# generator2.net
KiCad netlist of a schematic drawn in EAGLE
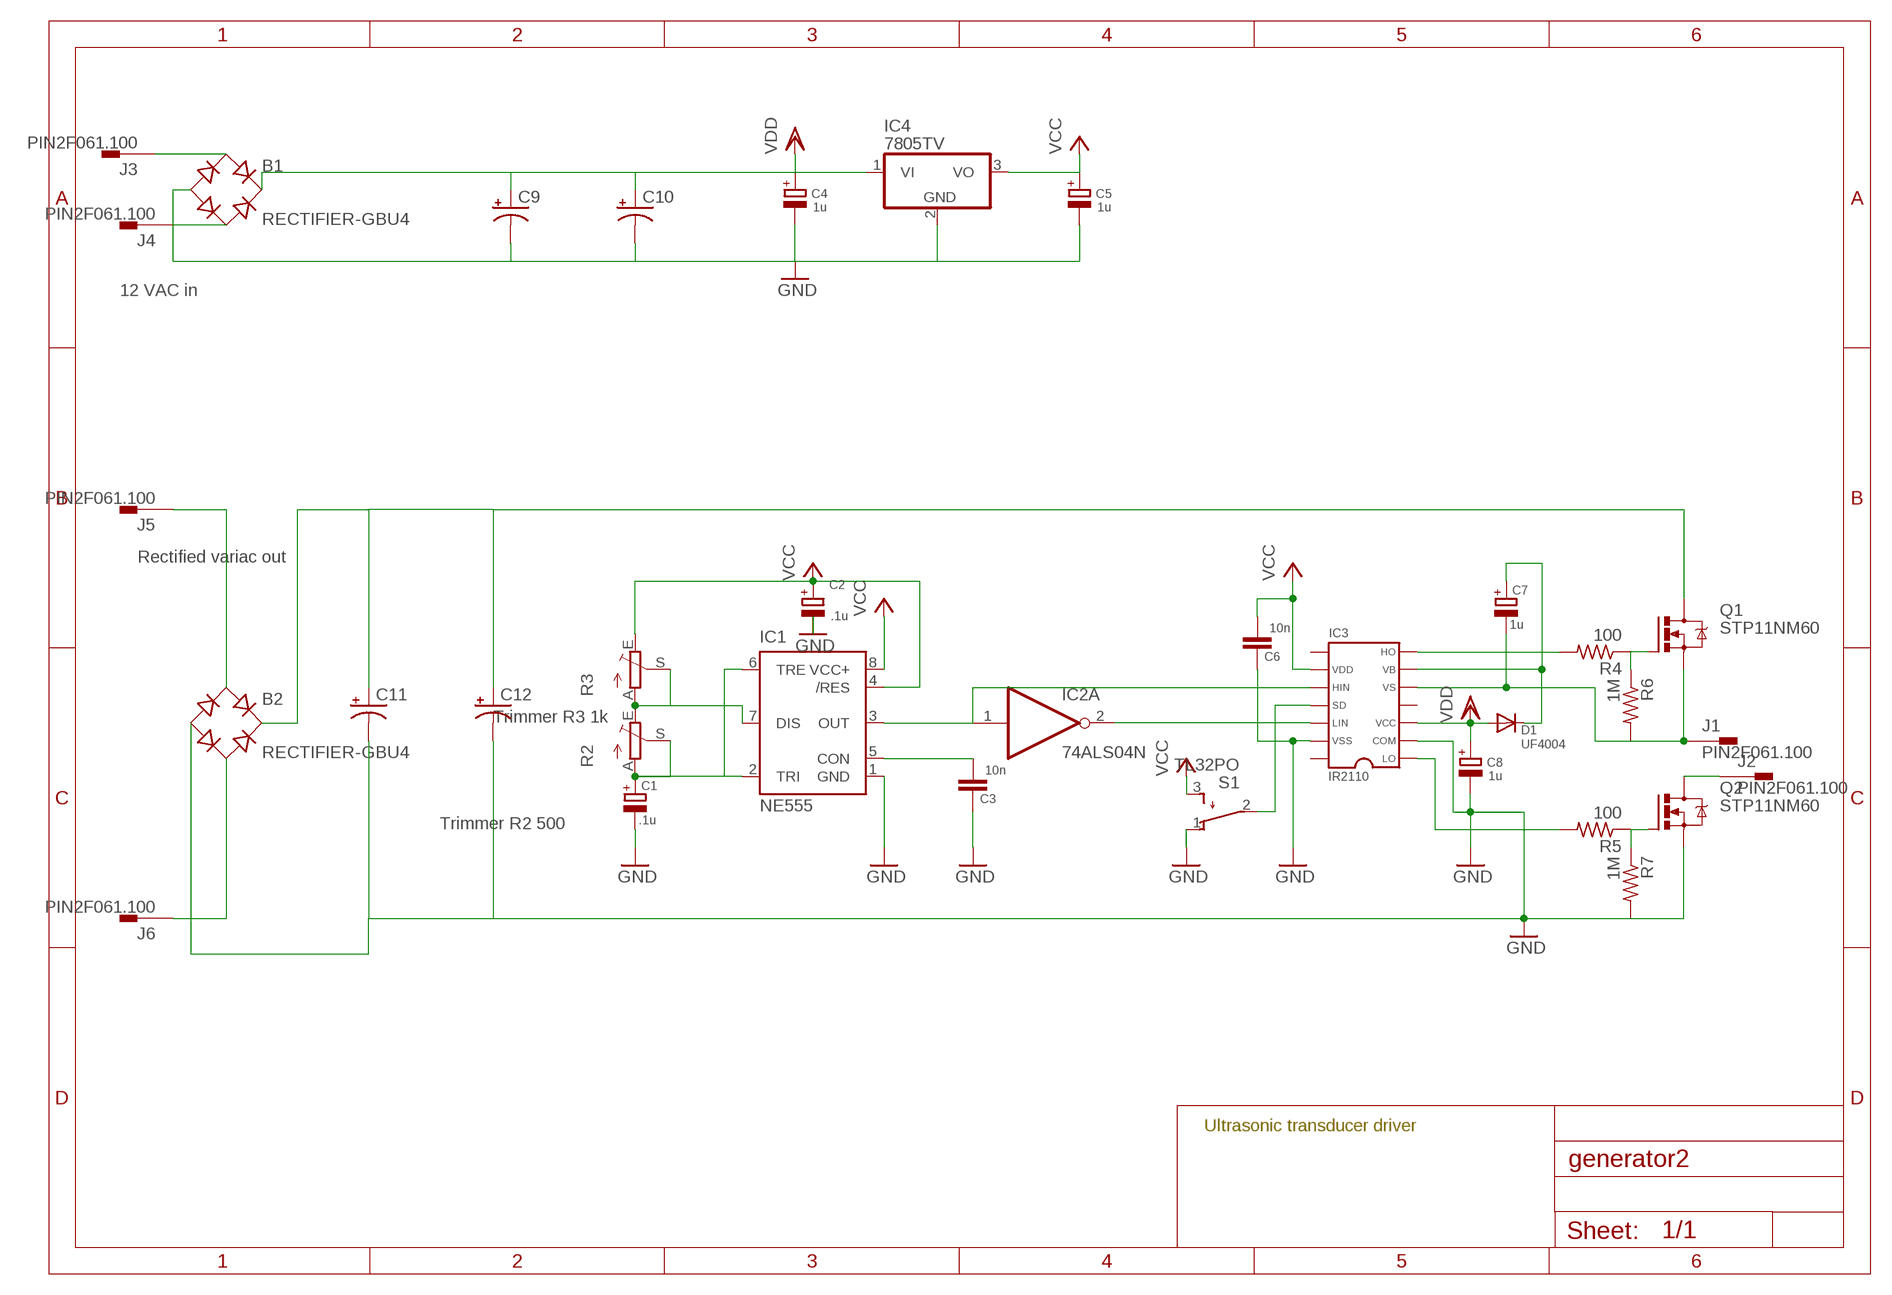
[diagram p0: schematic, sheet 1]

(export (version "E")
  (design (tool "Eeschema 10.0.6"))
  (components
    (comp (ref "B1")
      (value "RECTIFIER-GBU4")
      (footprint "eagle-import:GBU4")
      (libsource (lib "eagle-import") (part "RECTIFIER-GBU4"))
    )
    (comp (ref "B2")
      (value "RECTIFIER-GBU4")
      (footprint "eagle-import:GBU4")
      (libsource (lib "eagle-import") (part "RECTIFIER-GBU4"))
    )
    (comp (ref "C1")
      (value ".1u")
      (footprint "eagle-import:E5-8,5")
      (libsource (lib "eagle-import") (part "CPOL-EUE5-8.5"))
    )
    (comp (ref "C2")
      (value ".1u")
      (footprint "eagle-import:E5-8,5")
      (libsource (lib "eagle-import") (part "CPOL-EUE5-8.5"))
    )
    (comp (ref "C3")
      (value "10n")
      (footprint "eagle-import:C075-052X106")
      (libsource (lib "eagle-import") (part "C-EU075-052X106"))
    )
    (comp (ref "C4")
      (value "1u")
      (footprint "eagle-import:E5-8,5")
      (libsource (lib "eagle-import") (part "CPOL-EUE5-8.5"))
    )
    (comp (ref "C5")
      (value "1u")
      (footprint "eagle-import:E5-8,5")
      (libsource (lib "eagle-import") (part "CPOL-EUE5-8.5"))
    )
    (comp (ref "C6")
      (value "10n")
      (footprint "eagle-import:C075-052X106")
      (libsource (lib "eagle-import") (part "C-EU075-052X106"))
    )
    (comp (ref "C7")
      (value "1u")
      (footprint "eagle-import:E5-8,5")
      (libsource (lib "eagle-import") (part "CPOL-EUE5-8.5"))
    )
    (comp (ref "C8")
      (value "1u")
      (footprint "eagle-import:E5-8,5")
      (libsource (lib "eagle-import") (part "CPOL-EUE5-8.5"))
    )
    (comp (ref "C9")
      (value "CPOL-USE7.5-18")
      (footprint "eagle-import:E7,5-18")
      (libsource (lib "eagle-import") (part "CPOL-USE7.5-18"))
    )
    (comp (ref "C10")
      (value "CPOL-USE7.5-18")
      (footprint "eagle-import:E7,5-18")
      (libsource (lib "eagle-import") (part "CPOL-USE7.5-18"))
    )
    (comp (ref "C11")
      (value "CPOL-USE7.5-18")
      (footprint "eagle-import:E7,5-18")
      (libsource (lib "eagle-import") (part "CPOL-USE7.5-18"))
    )
    (comp (ref "C12")
      (value "CPOL-USE7.5-18")
      (footprint "eagle-import:E7,5-18")
      (libsource (lib "eagle-import") (part "CPOL-USE7.5-18"))
    )
    (comp (ref "D1")
      (value "UF4004")
      (footprint "eagle-import:D-7.5")
      (libsource (lib "eagle-import") (part "DIODE-D-7.5"))
    )
    (comp (ref "IC1")
      (value "NE555")
      (footprint "eagle-import:DIL-08")
      (fields (field (name "MF") "Arrow Electronics") (field (name "MPN") "NE555N"))
      (libsource (lib "eagle-import") (part "NE555"))
    )
    (comp (ref "IC2")
      (value "74ALS04N")
      (footprint "eagle-import:DIL14")
      (libsource (lib "eagle-import") (part "7404NALS"))
    )
    (comp (ref "IC3")
      (value "IR2110")
      (footprint "eagle-import:DIL14")
      (libsource (lib "eagle-import") (part "IR2110"))
    )
    (comp (ref "IC4")
      (value "7805TV")
      (footprint "eagle-import:TO220V")
      (libsource (lib "eagle-import") (part "78TV05"))
    )
    (comp (ref "J1")
      (value "PIN2F061.100")
      (footprint "eagle-import:F061.100")
      (libsource (lib "eagle-import") (part "PIN2F061.100"))
    )
    (comp (ref "J2")
      (value "PIN2F061.100")
      (footprint "eagle-import:F061.100")
      (libsource (lib "eagle-import") (part "PIN2F061.100"))
    )
    (comp (ref "J3")
      (value "PIN2F061.100")
      (footprint "eagle-import:F061.100")
      (libsource (lib "eagle-import") (part "PIN2F061.100"))
    )
    (comp (ref "J4")
      (value "PIN2F061.100")
      (footprint "eagle-import:F061.100")
      (libsource (lib "eagle-import") (part "PIN2F061.100"))
    )
    (comp (ref "J5")
      (value "PIN2F061.100")
      (footprint "eagle-import:F061.100")
      (libsource (lib "eagle-import") (part "PIN2F061.100"))
    )
    (comp (ref "J6")
      (value "PIN2F061.100")
      (footprint "eagle-import:F061.100")
      (libsource (lib "eagle-import") (part "PIN2F061.100"))
    )
    (comp (ref "Q1")
      (value "STP11NM60")
      (footprint "eagle-import:TO220BV")
      (libsource (lib "eagle-import") (part "IRF530"))
    )
    (comp (ref "Q2")
      (value "STP11NM60")
      (footprint "eagle-import:TO220BV")
      (libsource (lib "eagle-import") (part "IRF530"))
    )
    (comp (ref "R2")
      (value "TRIM_EU-LI10")
      (footprint "eagle-import:LI10")
      (libsource (lib "eagle-import") (part "TRIM_EU-LI10"))
    )
    (comp (ref "R3")
      (value "TRIM_EU-LI10")
      (footprint "eagle-import:LI10")
      (libsource (lib "eagle-import") (part "TRIM_EU-LI10"))
    )
    (comp (ref "R4")
      (value "100")
      (footprint "eagle-import:0207_10")
      (libsource (lib "eagle-import") (part "R-US_0207/10"))
    )
    (comp (ref "R5")
      (value "100")
      (footprint "eagle-import:0207_10")
      (libsource (lib "eagle-import") (part "R-US_0207/10"))
    )
    (comp (ref "R6")
      (value "1M")
      (footprint "eagle-import:0207_10")
      (libsource (lib "eagle-import") (part "R-US_0207/10"))
    )
    (comp (ref "R7")
      (value "1M")
      (footprint "eagle-import:0207_10")
      (libsource (lib "eagle-import") (part "R-US_0207/10"))
    )
    (comp (ref "S1")
      (value "TL32PO")
      (footprint "eagle-import:TL3XPO")
      (libsource (lib "eagle-import") (part "TL32PO"))
    )
  )
  (nets
    (net (code "1") (name "GND") (class "Default")
      (node (ref "B1") (pin "-") (pinfunction "-_-") (pintype "passive"))
      (node (ref "B2") (pin "-") (pinfunction "-_-") (pintype "passive"))
      (node (ref "C1") (pin "-") (pinfunction "-_-") (pintype "passive"))
      (node (ref "C10") (pin "-") (pinfunction "-_-") (pintype "passive"))
      (node (ref "C11") (pin "-") (pinfunction "-_-") (pintype "passive"))
      (node (ref "C12") (pin "-") (pinfunction "-_-") (pintype "passive"))
      (node (ref "C2") (pin "-") (pinfunction "-_-") (pintype "passive"))
      (node (ref "C3") (pin "1") (pinfunction "1_1") (pintype "passive"))
      (node (ref "C4") (pin "-") (pinfunction "-_-") (pintype "passive"))
      (node (ref "C5") (pin "-") (pinfunction "-_-") (pintype "passive"))
      (node (ref "C6") (pin "1") (pinfunction "1_1") (pintype "passive"))
      (node (ref "C8") (pin "-") (pinfunction "-_-") (pintype "passive"))
      (node (ref "C9") (pin "-") (pinfunction "-_-") (pintype "passive"))
      (node (ref "IC1") (pin "1") (pinfunction "GND_1") (pintype "power_in"))
      (node (ref "IC3") (pin "13") (pinfunction "13_13") (pintype "passive"))
      (node (ref "IC3") (pin "2") (pinfunction "2_2") (pintype "passive"))
      (node (ref "IC4") (pin "2") (pinfunction "GND_2") (pintype "passive"))
      (node (ref "Q2") (pin "S") (pinfunction "S_S") (pintype "passive"))
      (node (ref "R7") (pin "2") (pinfunction "2_2") (pintype "passive"))
      (node (ref "S1") (pin "1") (pinfunction "O_1") (pintype "passive"))
    )
    (net (code "2") (name "Net-(B1-PadAC1)") (class "Default")
      (node (ref "B1") (pin "AC1") (pinfunction "AC1_AC1") (pintype "passive"))
      (node (ref "J3") (pin "A1") (pinfunction "1_A1") (pintype "passive"))
      (node (ref "J3") (pin "A2") (pinfunction "1_A2") (pintype "passive"))
    )
    (net (code "3") (name "Net-(B1-PadAC2)") (class "Default")
      (node (ref "B1") (pin "AC2") (pinfunction "AC2_AC2") (pintype "passive"))
      (node (ref "J4") (pin "A1") (pinfunction "1_A1") (pintype "passive"))
      (node (ref "J4") (pin "A2") (pinfunction "1_A2") (pintype "passive"))
    )
    (net (code "4") (name "Net-(B2-Pad+)") (class "Default")
      (node (ref "B2") (pin "+") (pinfunction "+_+") (pintype "passive"))
      (node (ref "C11") (pin "+") (pinfunction "+_+") (pintype "passive"))
      (node (ref "C12") (pin "+") (pinfunction "+_+") (pintype "passive"))
      (node (ref "Q1") (pin "D") (pinfunction "D_D") (pintype "passive"))
    )
    (net (code "5") (name "Net-(B2-PadAC1)") (class "Default")
      (node (ref "B2") (pin "AC1") (pinfunction "AC1_AC1") (pintype "passive"))
      (node (ref "J5") (pin "A1") (pinfunction "1_A1") (pintype "passive"))
      (node (ref "J5") (pin "A2") (pinfunction "1_A2") (pintype "passive"))
    )
    (net (code "6") (name "Net-(B2-PadAC2)") (class "Default")
      (node (ref "B2") (pin "AC2") (pinfunction "AC2_AC2") (pintype "passive"))
      (node (ref "J6") (pin "A1") (pinfunction "1_A1") (pintype "passive"))
      (node (ref "J6") (pin "A2") (pinfunction "1_A2") (pintype "passive"))
    )
    (net (code "7") (name "Net-(C7-Pad+)") (class "Default")
      (node (ref "C7") (pin "+") (pinfunction "+_+") (pintype "passive"))
      (node (ref "D1") (pin "C") (pinfunction "C_C") (pintype "passive"))
      (node (ref "IC3") (pin "6") (pinfunction "6_6") (pintype "passive"))
    )
    (net (code "8") (name "Net-(C7-Pad-)") (class "Default")
      (node (ref "C7") (pin "-") (pinfunction "-_-") (pintype "passive"))
      (node (ref "IC3") (pin "5") (pinfunction "5_5") (pintype "passive"))
      (node (ref "J1") (pin "A1") (pinfunction "1_A1") (pintype "passive"))
      (node (ref "J1") (pin "A2") (pinfunction "1_A2") (pintype "passive"))
      (node (ref "Q1") (pin "S") (pinfunction "S_S") (pintype "passive"))
      (node (ref "R6") (pin "2") (pinfunction "2_2") (pintype "passive"))
    )
    (net (code "9") (name "Net-(IC1-CON)") (class "Default")
      (node (ref "C3") (pin "2") (pinfunction "2_2") (pintype "passive"))
      (node (ref "IC1") (pin "5") (pinfunction "CON_5") (pintype "input"))
    )
    (net (code "10") (name "Net-(IC1-DIS)") (class "Default")
      (node (ref "IC1") (pin "7") (pinfunction "DIS_7") (pintype "input"))
      (node (ref "R2") (pin "E") (pinfunction "E_E") (pintype "passive"))
      (node (ref "R3") (pin "A") (pinfunction "A_A") (pintype "passive"))
      (node (ref "R3") (pin "S") (pinfunction "S_S") (pintype "passive"))
    )
    (net (code "11") (name "Net-(IC1-OUT)") (class "Default")
      (node (ref "IC1") (pin "3") (pinfunction "OUT_3") (pintype "output"))
      (node (ref "IC2") (pin "1") (pinfunction "I_1") (pintype "input"))
      (node (ref "IC3") (pin "10") (pinfunction "10_10") (pintype "passive"))
    )
    (net (code "12") (name "Net-(IC1-TRE)") (class "Default")
      (node (ref "C1") (pin "+") (pinfunction "+_+") (pintype "passive"))
      (node (ref "IC1") (pin "2") (pinfunction "TRI_2") (pintype "input"))
      (node (ref "IC1") (pin "6") (pinfunction "TRE_6") (pintype "input"))
      (node (ref "R2") (pin "A") (pinfunction "A_A") (pintype "passive"))
      (node (ref "R2") (pin "S") (pinfunction "S_S") (pintype "passive"))
    )
    (net (code "13") (name "Net-(IC2A-O)") (class "Default")
      (node (ref "IC2") (pin "2") (pinfunction "O_2") (pintype "output"))
      (node (ref "IC3") (pin "12") (pinfunction "12_12") (pintype "passive"))
    )
    (net (code "14") (name "Net-(IC3-Pad1)") (class "Default")
      (node (ref "IC3") (pin "1") (pinfunction "1_1") (pintype "passive"))
      (node (ref "R5") (pin "2") (pinfunction "2_2") (pintype "passive"))
    )
    (net (code "15") (name "Net-(IC3-Pad7)") (class "Default")
      (node (ref "IC3") (pin "7") (pinfunction "7_7") (pintype "passive"))
      (node (ref "R4") (pin "2") (pinfunction "2_2") (pintype "passive"))
    )
    (net (code "16") (name "Net-(J2-1-PadA1)") (class "Default")
      (node (ref "J2") (pin "A1") (pinfunction "1_A1") (pintype "passive"))
      (node (ref "J2") (pin "A2") (pinfunction "1_A2") (pintype "passive"))
      (node (ref "Q2") (pin "D") (pinfunction "D_D") (pintype "passive"))
    )
    (net (code "17") (name "Net-(Q1-PadG)") (class "Default")
      (node (ref "Q1") (pin "G") (pinfunction "G_G") (pintype "passive"))
      (node (ref "R4") (pin "1") (pinfunction "1_1") (pintype "passive"))
      (node (ref "R6") (pin "1") (pinfunction "1_1") (pintype "passive"))
    )
    (net (code "18") (name "Net-(Q2-PadG)") (class "Default")
      (node (ref "Q2") (pin "G") (pinfunction "G_G") (pintype "passive"))
      (node (ref "R5") (pin "1") (pinfunction "1_1") (pintype "passive"))
      (node (ref "R7") (pin "1") (pinfunction "1_1") (pintype "passive"))
    )
    (net (code "19") (name "Net-(S1-P)") (class "Default")
      (node (ref "IC3") (pin "11") (pinfunction "11_11") (pintype "passive"))
      (node (ref "S1") (pin "2") (pinfunction "P_2") (pintype "passive"))
    )
    (net (code "20") (name "VCC") (class "Default")
      (node (ref "C2") (pin "+") (pinfunction "+_+") (pintype "passive"))
      (node (ref "C5") (pin "+") (pinfunction "+_+") (pintype "passive"))
      (node (ref "C6") (pin "2") (pinfunction "2_2") (pintype "passive"))
      (node (ref "IC1") (pin "4") (pinfunction "/RES_4") (pintype "input"))
      (node (ref "IC1") (pin "8") (pinfunction "VCC+_8") (pintype "power_in"))
      (node (ref "IC3") (pin "9") (pinfunction "9_9") (pintype "passive"))
      (node (ref "IC4") (pin "3") (pinfunction "VO_3") (pintype "passive"))
      (node (ref "R3") (pin "E") (pinfunction "E_E") (pintype "passive"))
      (node (ref "S1") (pin "3") (pinfunction "S_3") (pintype "passive"))
    )
    (net (code "21") (name "VDD") (class "Default")
      (node (ref "B1") (pin "+") (pinfunction "+_+") (pintype "passive"))
      (node (ref "C10") (pin "+") (pinfunction "+_+") (pintype "passive"))
      (node (ref "C4") (pin "+") (pinfunction "+_+") (pintype "passive"))
      (node (ref "C8") (pin "+") (pinfunction "+_+") (pintype "passive"))
      (node (ref "C9") (pin "+") (pinfunction "+_+") (pintype "passive"))
      (node (ref "D1") (pin "A") (pinfunction "A_A") (pintype "passive"))
      (node (ref "IC3") (pin "3") (pinfunction "3_3") (pintype "passive"))
      (node (ref "IC4") (pin "1") (pinfunction "VI_1") (pintype "input"))
    )
    (net (code "22") (name "unconnected-(IC3-Pad4)") (class "Default")
      (node (ref "IC3") (pin "4") (pinfunction "4_4") (pintype "passive"))
    )
    (net (code "23") (name "unconnected-(IC3-Pad8)") (class "Default")
      (node (ref "IC3") (pin "8") (pinfunction "8_8") (pintype "passive"))
    )
    (net (code "24") (name "unconnected-(IC3-Pad14)") (class "Default")
      (node (ref "IC3") (pin "14") (pinfunction "14_14") (pintype "passive"))
    )
  )
)
